# POWER.net
KiCad netlist of a schematic drawn in Altium Designer
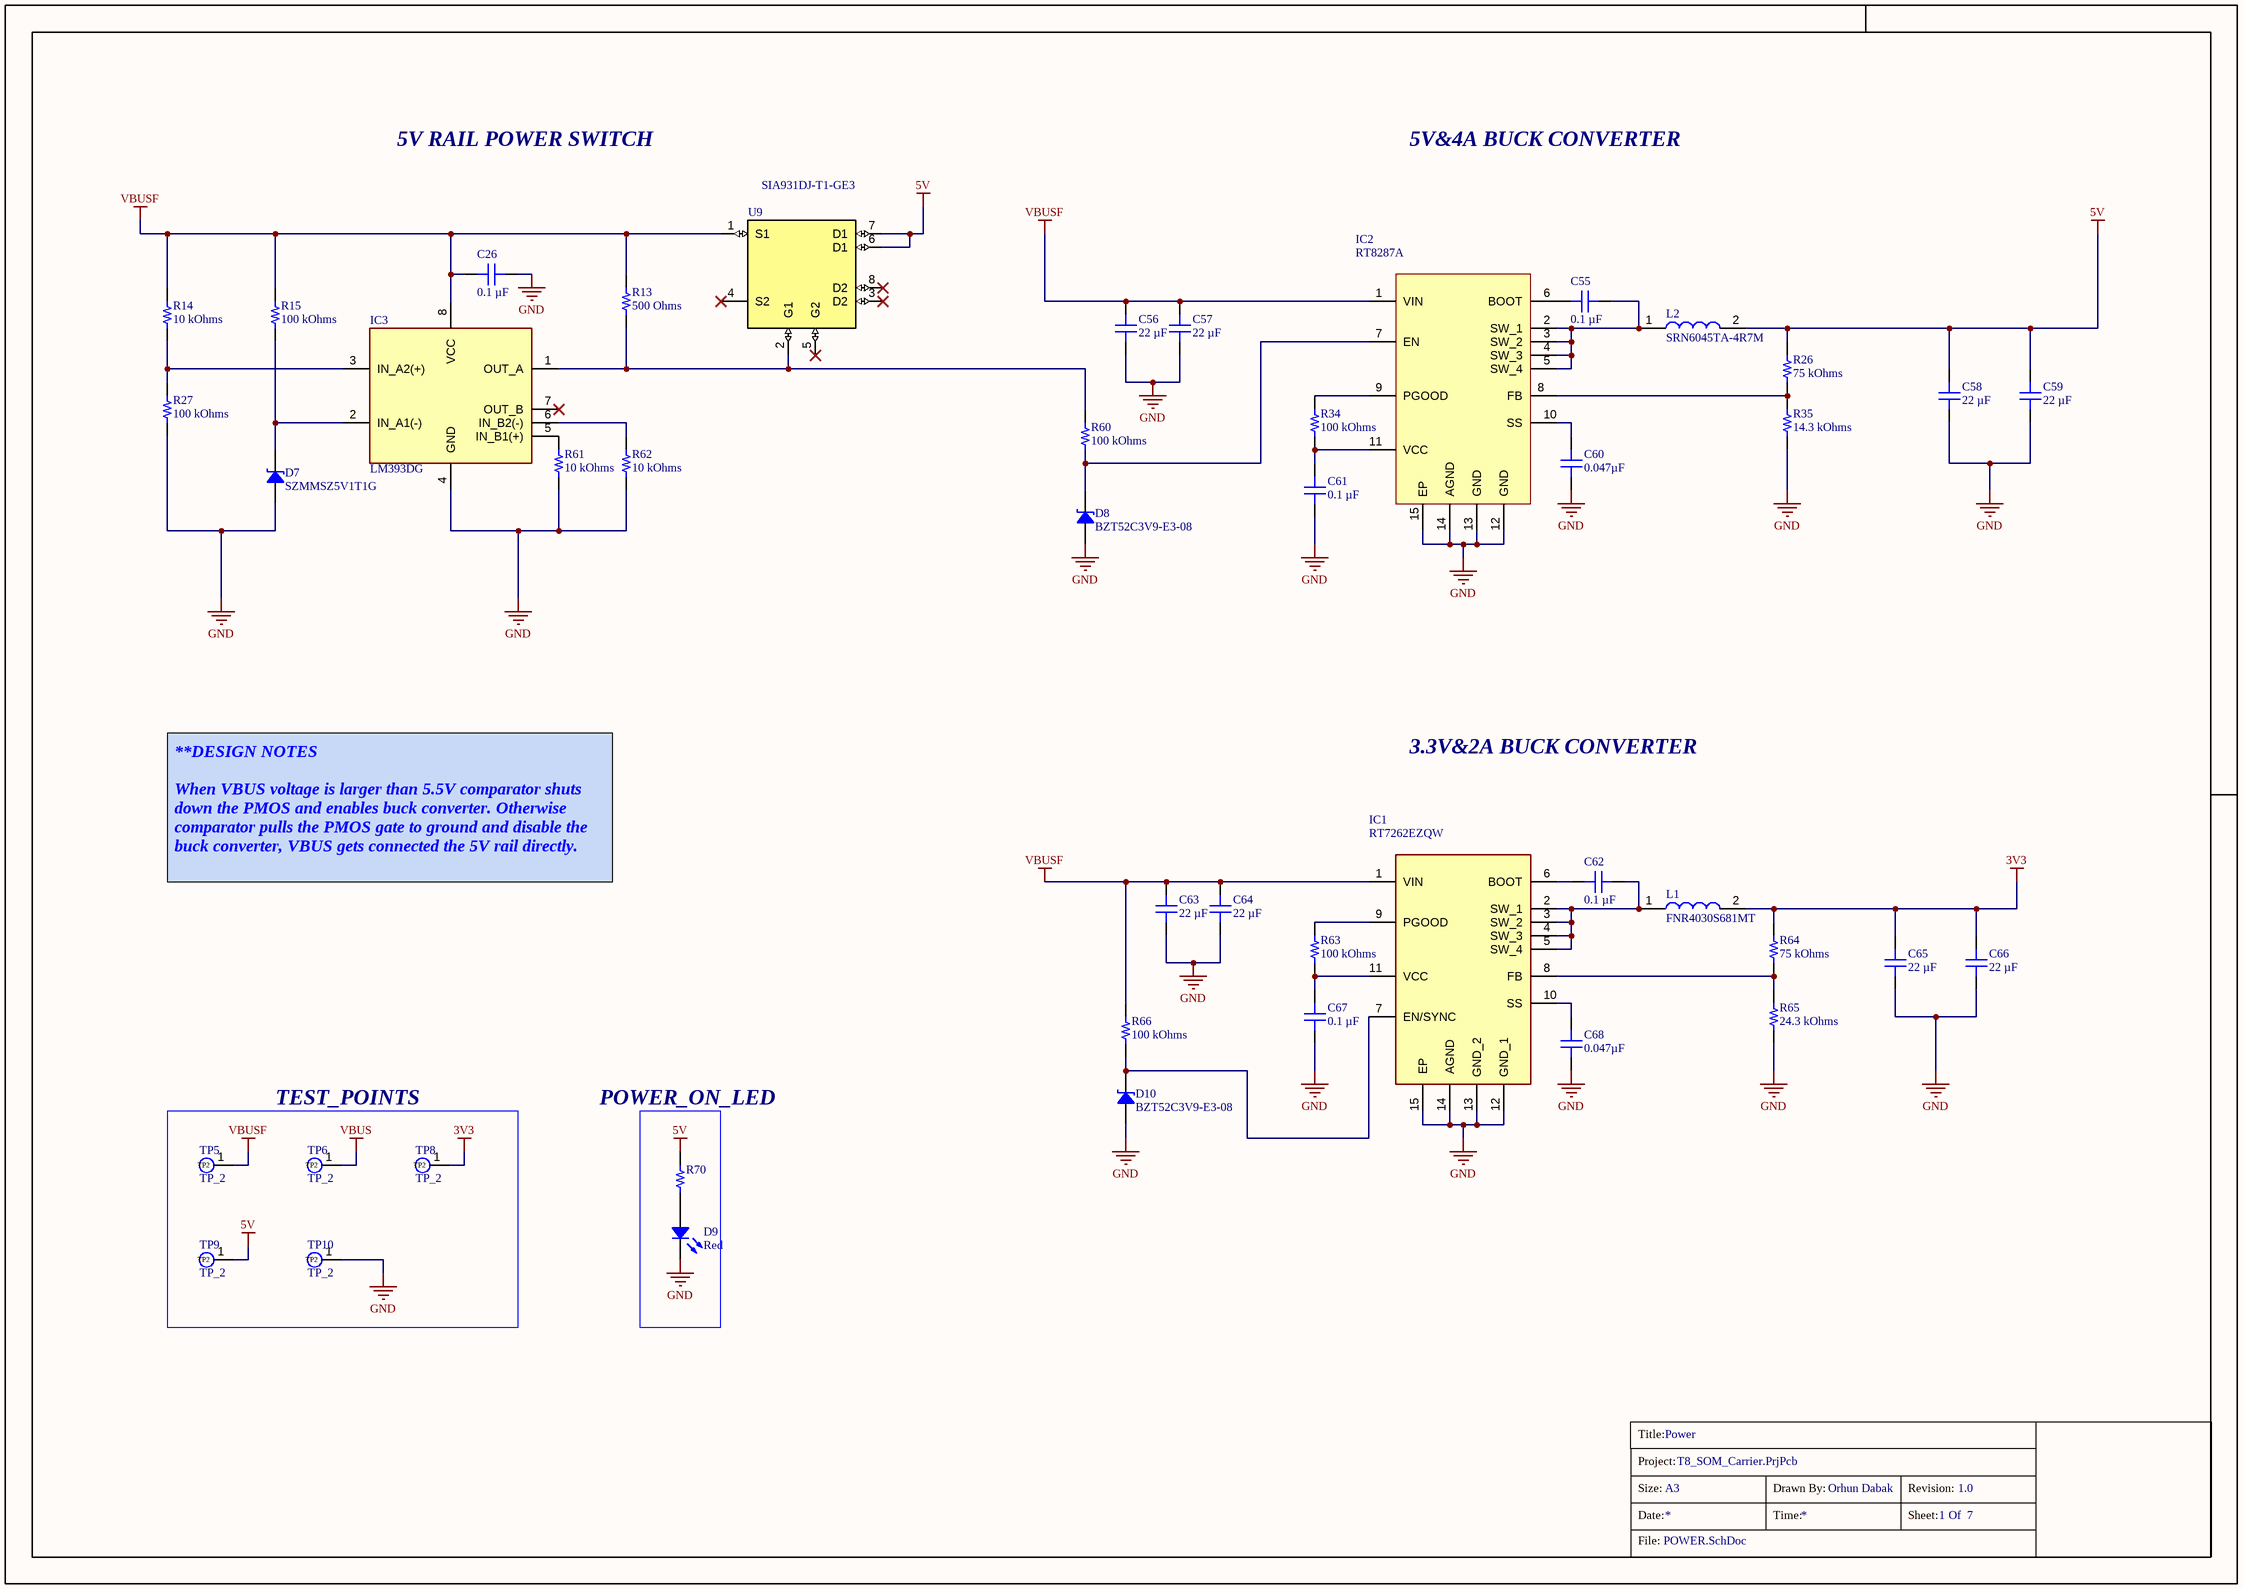
[diagram p0: POWER.SchDoc]

(export (version "E")
  (design (tool "Eeschema 10.0.6"))
  (components
    (comp (ref "C26")
      (value "0.1 µF")
      (footprint "CAP 0402_1005")
      (description "CAP CER 0.1UF 25V X7R 0402")
      (fields
        (field (name "PART NUMBER") "GCM155R71E104KE02D")
        (field (name "MANUFACTURER") "Murata Electronics")
      )
      (libsource (lib "Celestial Altium Library - altium_library") (part "Capacitor"))
    )
    (comp (ref "C55")
      (value "0.1 µF")
      (footprint "CAP 0402_1005")
      (description "CAP CER 0402 0.1UF 16V X7R 10%")
      (fields (field (name "PART NUMBER") "C0402C104K4RECAUTO") (field (name "MANUFACTURER") "KEMET"))
      (libsource (lib "Celestial Altium Library - altium_library") (part "Capacitor"))
    )
    (comp (ref "C56")
      (value "22 µF")
      (footprint "CAP 1812_4532 1.1MM")
      (description "CAP CER 22UF 25V X7R 1812")
      (fields
        (field (name "PART NUMBER") "CGA8P1X7R1E226M250KC")
        (field (name "MANUFACTURER") "TDK Corporation")
      )
      (libsource (lib "Celestial Altium Library - altium_library") (part "Capacitor"))
    )
    (comp (ref "C57")
      (value "22 µF")
      (footprint "CAP 1812_4532 1.1MM")
      (description "CAP CER 22UF 25V X7R 1812")
      (fields
        (field (name "PART NUMBER") "CGA8P1X7R1E226M250KC")
        (field (name "MANUFACTURER") "TDK Corporation")
      )
      (libsource (lib "Celestial Altium Library - altium_library") (part "Capacitor"))
    )
    (comp (ref "C58")
      (value "22 µF")
      (footprint "CAP 1210_3225 - 1MM")
      (description "CAP CER 22UF 16V X5R 1210")
      (fields
        (field (name "PART NUMBER") "C3225X5R1C226M250AA")
        (field (name "MANUFACTURER") "TDK Corporation")
      )
      (libsource (lib "Celestial Altium Library - altium_library") (part "Capacitor"))
    )
    (comp (ref "C59")
      (value "22 µF")
      (footprint "CAP 1210_3225 - 1MM")
      (description "CAP CER 22UF 16V X5R 1210")
      (fields
        (field (name "PART NUMBER") "C3225X5R1C226M250AA")
        (field (name "MANUFACTURER") "TDK Corporation")
      )
      (libsource (lib "Celestial Altium Library - altium_library") (part "Capacitor"))
    )
    (comp (ref "C60")
      (value "0.047µF")
      (footprint "CAP 0402_1005")
      (description "CAP CER 0.047UF 16V X5R 0402")
      (fields (field (name "PART NUMBER") "0402YD473KAT2A") (field (name "MANUFACTURER") "AVX Corporation"))
      (libsource (lib "Celestial Altium Library - altium_library") (part "Capacitor"))
    )
    (comp (ref "C61")
      (value "0.1 µF")
      (footprint "CAP 0402_1005")
      (description "CAP CER 0402 0.1UF 16V X7R 10%")
      (fields (field (name "PART NUMBER") "C0402C104K4RECAUTO") (field (name "MANUFACTURER") "KEMET"))
      (libsource (lib "Celestial Altium Library - altium_library") (part "Capacitor"))
    )
    (comp (ref "C62")
      (value "0.1 µF")
      (footprint "CAP 0402_1005")
      (description "CAP CER 0402 0.1UF 16V X7R 10%")
      (fields (field (name "PART NUMBER") "C0402C104K4RECAUTO") (field (name "MANUFACTURER") "KEMET"))
      (libsource (lib "Celestial Altium Library - altium_library") (part "Capacitor"))
    )
    (comp (ref "C63")
      (value "22 µF")
      (footprint "CAP 1812_4532 1.1MM")
      (description "CAP CER 22UF 25V X7R 1812")
      (fields
        (field (name "PART NUMBER") "CGA8P1X7R1E226M250KC")
        (field (name "MANUFACTURER") "TDK Corporation")
      )
      (libsource (lib "Celestial Altium Library - altium_library") (part "Capacitor"))
    )
    (comp (ref "C64")
      (value "22 µF")
      (footprint "CAP 1812_4532 1.1MM")
      (description "CAP CER 22UF 25V X7R 1812")
      (fields
        (field (name "PART NUMBER") "CGA8P1X7R1E226M250KC")
        (field (name "MANUFACTURER") "TDK Corporation")
      )
      (libsource (lib "Celestial Altium Library - altium_library") (part "Capacitor"))
    )
    (comp (ref "C65")
      (value "22 µF")
      (footprint "CAP 1210_3225 - 1MM")
      (description "CAP CER 22UF 16V X5R 1210")
      (fields
        (field (name "PART NUMBER") "C3225X5R1C226M250AA")
        (field (name "MANUFACTURER") "TDK Corporation")
      )
      (libsource (lib "Celestial Altium Library - altium_library") (part "Capacitor"))
    )
    (comp (ref "C66")
      (value "22 µF")
      (footprint "CAP 1210_3225 - 1MM")
      (description "CAP CER 22UF 16V X5R 1210")
      (fields
        (field (name "PART NUMBER") "C3225X5R1C226M250AA")
        (field (name "MANUFACTURER") "TDK Corporation")
      )
      (libsource (lib "Celestial Altium Library - altium_library") (part "Capacitor"))
    )
    (comp (ref "C67")
      (value "0.1 µF")
      (footprint "CAP 0402_1005")
      (description "CAP CER 0402 0.1UF 16V X7R 10%")
      (fields (field (name "PART NUMBER") "C0402C104K4RECAUTO") (field (name "MANUFACTURER") "KEMET"))
      (libsource (lib "Celestial Altium Library - altium_library") (part "Capacitor"))
    )
    (comp (ref "C68")
      (value "0.047µF")
      (footprint "CAP 0402_1005")
      (description "CAP CER 0.047UF 16V X5R 0402")
      (fields (field (name "PART NUMBER") "0402YD473KAT2A") (field (name "MANUFACTURER") "AVX Corporation"))
      (libsource (lib "Celestial Altium Library - altium_library") (part "Capacitor"))
    )
    (comp (ref "D7")
      (value "SZMMSZ5V1T1G")
      (footprint "SOD-123")
      (description "DIODE ZENER 5.1V 500MW SOD123")
      (fields (field (name "MANUFACTURER") "ON Semiconductor") (field (name "TOLERANCE") "±5%"))
      (libsource (lib "Celestial Altium Library - altium_library") (part "Diode Zener"))
    )
    (comp (ref "D8")
      (value "BZT52C3V9-E3-08")
      (footprint "SOD-123")
      (description "DIODE ZENER 3.9V 410MW SOD123")
      (fields
        (field (name "MANUFACTURER") "Vishay Semiconductor Diodes Division")
        (field (name "TOLERANCE") "±5%")
      )
      (libsource (lib "Celestial Altium Library - altium_library") (part "Diode Zener"))
    )
    (comp (ref "D9")
      (value "Red")
      (footprint "LED 0603_1608 RED")
      (description "LED RED CLEAR CHIP SMD")
      (fields (field (name "PART NUMBER") "LTST-C193KRKT-2A") (field (name "MANUFACTURER") "Lite-On Inc."))
      (libsource (lib "Celestial Altium Library - altium_library") (part "LED"))
    )
    (comp (ref "D10")
      (value "BZT52C3V9-E3-08")
      (footprint "SOD-123")
      (description "DIODE ZENER 3.9V 410MW SOD123")
      (fields
        (field (name "MANUFACTURER") "Vishay Semiconductor Diodes Division")
        (field (name "TOLERANCE") "±5%")
      )
      (libsource (lib "Celestial Altium Library - altium_library") (part "Diode Zener"))
    )
    (comp (ref "IC1")
      (value "RT7262EZQW")
      (footprint "SamacSys:SON50P300X400X80-15N")
      (description "Integrated Circuit")
      (libsource (lib "SamacSys") (part "RT7262EZQW"))
    )
    (comp (ref "IC2")
      (value "RT8287A")
      (footprint "SamacSys:SON50P300X400X80-15N")
      (description "Integrated Circuit")
      (libsource (lib "SamacSys") (part "RT8287A"))
    )
    (comp (ref "IC3")
      (value "LM393DG")
      (footprint "SamacSys:SOIC127P600X175-8N")
      (description "Integrated Circuit")
      (fields (field (name "MOUSER PART NUMBER") "863-LM393DG"))
      (libsource (lib "SamacSys") (part "LM393DG"))
    )
    (comp (ref "L1")
      (value "FNR4030S681MT")
      (footprint "SamacSys:INDPM4040X300N")
      (description "Inductor")
      (libsource (lib "SamacSys") (part "FNR4030S681MT"))
    )
    (comp (ref "L2")
      (value "SRN6045TA-4R7M")
      (footprint "SamacSys:SRN6045TA4R7M")
      (description "Inductor")
      (fields (field (name "MOUSER PART NUMBER") "652-SRN6045TA-4R7M"))
      (libsource (lib "SamacSys") (part "SRN6045TA-4R7M"))
    )
    (comp (ref "R13")
      (value "500 Ohms")
      (footprint "RES 0603_1608")
      (description "RES SMD 500 OHM 0.05% 1/10W 0603")
      (fields (field (name "PART NUMBER") "TNPU0603500RAZEN00") (field (name "MANUFACTURER") "Vishay Dale"))
      (libsource (lib "Celestial Altium Library - altium_library") (part "Resistor"))
    )
    (comp (ref "R14")
      (value "10 kOhms")
      (footprint "RES 0402_1005")
      (description "RES 10K OHM 0.1% 1/10W 0402")
      (fields
        (field (name "PART NUMBER") "RP73PF1E10KBTD")
        (field (name "MANUFACTURER") "TE Connectivity Passive Product")
      )
      (libsource (lib "Celestial Altium Library - altium_library") (part "Resistor"))
    )
    (comp (ref "R15")
      (value "100 kOhms")
      (footprint "RES 0402_1005")
      (description "RES 100K OHM 0.1% 1/10W 0402")
      (fields
        (field (name "PART NUMBER") "RP73PF1E100KBTD")
        (field (name "MANUFACTURER") "TE Connectivity Passive Product")
      )
      (libsource (lib "Celestial Altium Library - altium_library") (part "Resistor"))
    )
    (comp (ref "R26")
      (value "75 kOhms")
      (footprint "RES 0402_1005")
      (description "RES 75K OHM 1% 1/16W 0402")
      (fields (field (name "PART NUMBER") "RC0402FR-0775KL") (field (name "MANUFACTURER") "Yageo"))
      (libsource (lib "Celestial Altium Library - altium_library") (part "Resistor"))
    )
    (comp (ref "R27")
      (value "100 kOhms")
      (footprint "RES 0402_1005")
      (description "RES 100K OHM 0.1% 1/10W 0402")
      (fields
        (field (name "PART NUMBER") "RP73PF1E100KBTD")
        (field (name "MANUFACTURER") "TE Connectivity Passive Product")
      )
      (libsource (lib "Celestial Altium Library - altium_library") (part "Resistor"))
    )
    (comp (ref "R34")
      (value "100 kOhms")
      (footprint "RES 0402_1005")
      (description "RES 100K OHM 0.1% 1/10W 0402")
      (fields
        (field (name "PART NUMBER") "RP73PF1E100KBTD")
        (field (name "MANUFACTURER") "TE Connectivity Passive Product")
      )
      (libsource (lib "Celestial Altium Library - altium_library") (part "Resistor"))
    )
    (comp (ref "R35")
      (value "14.3 kOhms")
      (footprint "RES 0402_1005")
      (description "RES 14.3 KOHMS 0.1% 1/16W 0402")
      (fields
        (field (name "PART NUMBER") "RQ73C1E14K3BTD")
        (field (name "MANUFACTURER") "TE Connectivity Passive Product")
      )
      (libsource (lib "Celestial Altium Library - altium_library") (part "Resistor"))
    )
    (comp (ref "R60")
      (value "100 kOhms")
      (footprint "RES 0402_1005")
      (description "RES 100K OHM 0.1% 1/10W 0402")
      (fields
        (field (name "PART NUMBER") "RP73PF1E100KBTD")
        (field (name "MANUFACTURER") "TE Connectivity Passive Product")
      )
      (libsource (lib "Celestial Altium Library - altium_library") (part "Resistor"))
    )
    (comp (ref "R61")
      (value "10 kOhms")
      (footprint "RES 0402_1005")
      (description "RES 10K OHM 0.1% 1/10W 0402")
      (fields
        (field (name "PART NUMBER") "RP73PF1E10KBTD")
        (field (name "MANUFACTURER") "TE Connectivity Passive Product")
      )
      (libsource (lib "Celestial Altium Library - altium_library") (part "Resistor"))
    )
    (comp (ref "R62")
      (value "10 kOhms")
      (footprint "RES 0402_1005")
      (description "RES 10K OHM 0.1% 1/10W 0402")
      (fields
        (field (name "PART NUMBER") "RP73PF1E10KBTD")
        (field (name "MANUFACTURER") "TE Connectivity Passive Product")
      )
      (libsource (lib "Celestial Altium Library - altium_library") (part "Resistor"))
    )
    (comp (ref "R63")
      (value "100 kOhms")
      (footprint "RES 0402_1005")
      (description "RES 100K OHM 0.1% 1/10W 0402")
      (fields
        (field (name "PART NUMBER") "RP73PF1E100KBTD")
        (field (name "MANUFACTURER") "TE Connectivity Passive Product")
      )
      (libsource (lib "Celestial Altium Library - altium_library") (part "Resistor"))
    )
    (comp (ref "R64")
      (value "75 kOhms")
      (footprint "RES 0402_1005")
      (description "RES 75K OHM 1% 1/16W 0402")
      (fields (field (name "PART NUMBER") "RC0402FR-0775KL") (field (name "MANUFACTURER") "Yageo"))
      (libsource (lib "Celestial Altium Library - altium_library") (part "Resistor"))
    )
    (comp (ref "R65")
      (value "24.3 kOhms")
      (footprint "RES 0402_1005")
      (description "RES 24.3K OHM 1% 1/16W 0402")
      (fields (field (name "PART NUMBER") "RC0402FR-0724K3L") (field (name "MANUFACTURER") "Yageo"))
      (libsource (lib "Celestial Altium Library - altium_library") (part "Resistor"))
    )
    (comp (ref "R66")
      (value "100 kOhms")
      (footprint "RES 0402_1005")
      (description "RES 100K OHM 0.1% 1/10W 0402")
      (fields
        (field (name "PART NUMBER") "RP73PF1E100KBTD")
        (field (name "MANUFACTURER") "TE Connectivity Passive Product")
      )
      (libsource (lib "Celestial Altium Library - altium_library") (part "Resistor"))
    )
    (comp (ref "R70")
      (value "1 kOhms")
      (footprint "RES 0402_1005")
      (description "RES SMD 1K OHM 1% 1/16W 0402")
      (fields (field (name "PART NUMBER") "AC0402FR-071KL") (field (name "MANUFACTURER") "Yageo"))
      (libsource (lib "Celestial Altium Library - altium_library") (part "Resistor"))
    )
    (comp (ref "TP5")
      (value "TP_2")
      (footprint "TEST POINT")
      (description "1.5x1.5mm Test Point")
      (libsource (lib "FPGA_Based_SOM") (part "TEST POINT_2"))
    )
    (comp (ref "TP6")
      (value "TP_2")
      (footprint "TEST POINT")
      (description "1.5x1.5mm Test Point")
      (libsource (lib "FPGA_Based_SOM") (part "TEST POINT_2"))
    )
    (comp (ref "TP8")
      (value "TP_2")
      (footprint "TEST POINT")
      (description "1.5x1.5mm Test Point")
      (libsource (lib "FPGA_Based_SOM") (part "TEST POINT_2"))
    )
    (comp (ref "TP9")
      (value "TP_2")
      (footprint "TEST POINT")
      (description "1.5x1.5mm Test Point")
      (libsource (lib "FPGA_Based_SOM") (part "TEST POINT_2"))
    )
    (comp (ref "TP10")
      (value "TP_2")
      (footprint "TEST POINT")
      (description "1.5x1.5mm Test Point")
      (libsource (lib "FPGA_Based_SOM") (part "TEST POINT_2"))
    )
    (comp (ref "U9")
      (value "SIA931DJ-T1-GE3")
      (footprint "SIA931DJ-T1-GE3:MOSFET_T1-GE3_VIS")
      (description "No Description Available")
      (fields (field (name "COPYRIGHT") "Copyright (C) 2022 Ultra Librarian. All rights reserved."))
      (libsource (lib "SIA931DJ-T1-GE3") (part "SIA931DJ-T1-GE3"))
    )
  )
  (nets
    (net (code "1") (name "3V3") (class "Default")
      (node (ref "C65") (pin "2") (pinfunction "2_2") (pintype "passive"))
      (node (ref "C66") (pin "2") (pinfunction "2_2") (pintype "passive"))
      (node (ref "L1") (pin "2") (pinfunction "2_2") (pintype "passive"))
      (node (ref "R64") (pin "1") (pinfunction "1_1") (pintype "passive"))
      (node (ref "TP8") (pin "1") (pinfunction "TP2_1") (pintype "passive"))
    )
    (net (code "2") (name "5V") (class "Default")
      (node (ref "C58") (pin "2") (pinfunction "2_2") (pintype "passive"))
      (node (ref "C59") (pin "2") (pinfunction "2_2") (pintype "passive"))
      (node (ref "L2") (pin "2") (pinfunction "2_2") (pintype "passive"))
      (node (ref "R26") (pin "1") (pinfunction "1_1") (pintype "passive"))
      (node (ref "R70") (pin "2") (pinfunction "2_2") (pintype "passive"))
      (node (ref "TP9") (pin "1") (pinfunction "TP2_1") (pintype "passive"))
      (node (ref "U9") (pin "6") (pinfunction "D1_6") (pintype "bidirectional"))
      (node (ref "U9") (pin "7") (pinfunction "D1_7") (pintype "bidirectional"))
    )
    (net (code "3") (name "GND") (class "Default")
      (node (ref "C26") (pin "1") (pinfunction "1_1") (pintype "passive"))
      (node (ref "C56") (pin "1") (pinfunction "1_1") (pintype "passive"))
      (node (ref "C57") (pin "1") (pinfunction "1_1") (pintype "passive"))
      (node (ref "C58") (pin "1") (pinfunction "1_1") (pintype "passive"))
      (node (ref "C59") (pin "1") (pinfunction "1_1") (pintype "passive"))
      (node (ref "C60") (pin "1") (pinfunction "1_1") (pintype "passive"))
      (node (ref "C61") (pin "1") (pinfunction "1_1") (pintype "passive"))
      (node (ref "C63") (pin "1") (pinfunction "1_1") (pintype "passive"))
      (node (ref "C64") (pin "1") (pinfunction "1_1") (pintype "passive"))
      (node (ref "C65") (pin "1") (pinfunction "1_1") (pintype "passive"))
      (node (ref "C66") (pin "1") (pinfunction "1_1") (pintype "passive"))
      (node (ref "C67") (pin "1") (pinfunction "1_1") (pintype "passive"))
      (node (ref "C68") (pin "1") (pinfunction "1_1") (pintype "passive"))
      (node (ref "D10") (pin "1") (pinfunction "1_1") (pintype "passive"))
      (node (ref "D7") (pin "1") (pinfunction "1_1") (pintype "passive"))
      (node (ref "D8") (pin "1") (pinfunction "1_1") (pintype "passive"))
      (node (ref "D9") (pin "2") (pinfunction "2_2") (pintype "passive"))
      (node (ref "IC1") (pin "12") (pinfunction "GND_1_12") (pintype "passive"))
      (node (ref "IC1") (pin "13") (pinfunction "GND_2_13") (pintype "passive"))
      (node (ref "IC1") (pin "14") (pinfunction "AGND_14") (pintype "passive"))
      (node (ref "IC1") (pin "15") (pinfunction "EP_15") (pintype "passive"))
      (node (ref "IC2") (pin "12") (pinfunction "GND_12") (pintype "passive"))
      (node (ref "IC2") (pin "13") (pinfunction "GND_13") (pintype "passive"))
      (node (ref "IC2") (pin "14") (pinfunction "AGND_14") (pintype "passive"))
      (node (ref "IC3") (pin "4") (pinfunction "GND_4") (pintype "passive"))
      (node (ref "R27") (pin "1") (pinfunction "1_1") (pintype "passive"))
      (node (ref "R35") (pin "1") (pinfunction "1_1") (pintype "passive"))
      (node (ref "R61") (pin "1") (pinfunction "1_1") (pintype "passive"))
      (node (ref "R62") (pin "1") (pinfunction "1_1") (pintype "passive"))
      (node (ref "R65") (pin "1") (pinfunction "1_1") (pintype "passive"))
      (node (ref "TP10") (pin "1") (pinfunction "TP2_1") (pintype "passive"))
    )
    (net (code "4") (name "Net-(D9-Pad1)") (class "Default")
      (node (ref "D9") (pin "1") (pinfunction "1_1") (pintype "passive"))
      (node (ref "R70") (pin "1") (pinfunction "1_1") (pintype "passive"))
    )
    (net (code "5") (name "Net-(IC1-BOOT)") (class "Default")
      (node (ref "C62") (pin "1") (pinfunction "1_1") (pintype "passive"))
      (node (ref "IC1") (pin "6") (pinfunction "BOOT_6") (pintype "passive"))
    )
    (net (code "6") (name "Net-(IC1-EN{slash}SYNC)") (class "Default")
      (node (ref "D10") (pin "2") (pinfunction "2_2") (pintype "passive"))
      (node (ref "IC1") (pin "7") (pinfunction "EN/SYNC_7") (pintype "passive"))
      (node (ref "R66") (pin "1") (pinfunction "1_1") (pintype "passive"))
    )
    (net (code "7") (name "Net-(IC1-FB)") (class "Default")
      (node (ref "IC1") (pin "8") (pinfunction "FB_8") (pintype "passive"))
      (node (ref "R64") (pin "2") (pinfunction "2_2") (pintype "passive"))
      (node (ref "R65") (pin "2") (pinfunction "2_2") (pintype "passive"))
    )
    (net (code "8") (name "Net-(IC1-PGOOD)") (class "Default")
      (node (ref "IC1") (pin "9") (pinfunction "PGOOD_9") (pintype "passive"))
      (node (ref "R63") (pin "2") (pinfunction "2_2") (pintype "passive"))
    )
    (net (code "9") (name "Net-(IC1-SS)") (class "Default")
      (node (ref "C68") (pin "2") (pinfunction "2_2") (pintype "passive"))
      (node (ref "IC1") (pin "10") (pinfunction "SS_10") (pintype "passive"))
    )
    (net (code "10") (name "Net-(IC1-SW_1)") (class "Default")
      (node (ref "C62") (pin "2") (pinfunction "2_2") (pintype "passive"))
      (node (ref "IC1") (pin "2") (pinfunction "SW_1_2") (pintype "passive"))
      (node (ref "IC1") (pin "3") (pinfunction "SW_2_3") (pintype "passive"))
      (node (ref "IC1") (pin "4") (pinfunction "SW_3_4") (pintype "passive"))
      (node (ref "IC1") (pin "5") (pinfunction "SW_4_5") (pintype "passive"))
      (node (ref "L1") (pin "1") (pinfunction "1_1") (pintype "passive"))
    )
    (net (code "11") (name "Net-(IC1-VCC)") (class "Default")
      (node (ref "C67") (pin "2") (pinfunction "2_2") (pintype "passive"))
      (node (ref "IC1") (pin "11") (pinfunction "VCC_11") (pintype "passive"))
      (node (ref "R63") (pin "1") (pinfunction "1_1") (pintype "passive"))
    )
    (net (code "12") (name "Net-(IC2-BOOT)") (class "Default")
      (node (ref "C55") (pin "1") (pinfunction "1_1") (pintype "passive"))
      (node (ref "IC2") (pin "6") (pinfunction "BOOT_6") (pintype "passive"))
    )
    (net (code "13") (name "Net-(IC2-EN)") (class "Default")
      (node (ref "D8") (pin "2") (pinfunction "2_2") (pintype "passive"))
      (node (ref "IC2") (pin "7") (pinfunction "EN_7") (pintype "passive"))
      (node (ref "R60") (pin "1") (pinfunction "1_1") (pintype "passive"))
    )
    (net (code "14") (name "Net-(IC2-PGOOD)") (class "Default")
      (node (ref "IC2") (pin "9") (pinfunction "PGOOD_9") (pintype "passive"))
      (node (ref "R34") (pin "2") (pinfunction "2_2") (pintype "passive"))
    )
    (net (code "15") (name "Net-(IC2-SS)") (class "Default")
      (node (ref "C60") (pin "2") (pinfunction "2_2") (pintype "passive"))
      (node (ref "IC2") (pin "10") (pinfunction "SS_10") (pintype "passive"))
    )
    (net (code "16") (name "Net-(IC2-SW_1)") (class "Default")
      (node (ref "C55") (pin "2") (pinfunction "2_2") (pintype "passive"))
      (node (ref "IC2") (pin "2") (pinfunction "SW_1_2") (pintype "passive"))
      (node (ref "IC2") (pin "3") (pinfunction "SW_2_3") (pintype "passive"))
      (node (ref "IC2") (pin "4") (pinfunction "SW_3_4") (pintype "passive"))
      (node (ref "IC2") (pin "5") (pinfunction "SW_4_5") (pintype "passive"))
      (node (ref "L2") (pin "1") (pinfunction "1_1") (pintype "passive"))
    )
    (net (code "17") (name "Net-(IC2-VCC)") (class "Default")
      (node (ref "C61") (pin "2") (pinfunction "2_2") (pintype "passive"))
      (node (ref "IC2") (pin "11") (pinfunction "VCC_11") (pintype "passive"))
      (node (ref "R34") (pin "1") (pinfunction "1_1") (pintype "passive"))
    )
    (net (code "18") (name "Net-(IC3-IN_A1(-))") (class "Default")
      (node (ref "D7") (pin "2") (pinfunction "2_2") (pintype "passive"))
      (node (ref "IC3") (pin "2") (pinfunction "IN_A1(-)_2") (pintype "passive"))
      (node (ref "R15") (pin "1") (pinfunction "1_1") (pintype "passive"))
    )
    (net (code "19") (name "Net-(IC3-IN_A2(+))") (class "Default")
      (node (ref "IC3") (pin "3") (pinfunction "IN_A2(+)_3") (pintype "passive"))
      (node (ref "R14") (pin "1") (pinfunction "1_1") (pintype "passive"))
      (node (ref "R27") (pin "2") (pinfunction "2_2") (pintype "passive"))
    )
    (net (code "20") (name "Net-(IC3-IN_B1(+))") (class "Default")
      (node (ref "IC3") (pin "5") (pinfunction "IN_B1(+)_5") (pintype "passive"))
      (node (ref "R61") (pin "2") (pinfunction "2_2") (pintype "passive"))
    )
    (net (code "21") (name "Net-(IC3-IN_B2(-))") (class "Default")
      (node (ref "IC3") (pin "6") (pinfunction "IN_B2(-)_6") (pintype "passive"))
      (node (ref "R62") (pin "2") (pinfunction "2_2") (pintype "passive"))
    )
    (net (code "22") (name "Net-(IC3-OUT_A)") (class "Default")
      (node (ref "IC3") (pin "1") (pinfunction "OUT_A_1") (pintype "passive"))
      (node (ref "R13") (pin "1") (pinfunction "1_1") (pintype "passive"))
      (node (ref "R60") (pin "2") (pinfunction "2_2") (pintype "passive"))
      (node (ref "U9") (pin "2") (pinfunction "G1_2") (pintype "bidirectional"))
    )
    (net (code "23") (name "Net-(R26-Pad2)") (class "Default")
      (node (ref "R26") (pin "2") (pinfunction "2_2") (pintype "passive"))
      (node (ref "R35") (pin "2") (pinfunction "2_2") (pintype "passive"))
    )
    (net (code "24") (name "VBUS") (class "Default")
      (node (ref "TP6") (pin "1") (pinfunction "TP2_1") (pintype "passive"))
    )
    (net (code "25") (name "VBUSF") (class "Default")
      (node (ref "C26") (pin "2") (pinfunction "2_2") (pintype "passive"))
      (node (ref "C56") (pin "2") (pinfunction "2_2") (pintype "passive"))
      (node (ref "C57") (pin "2") (pinfunction "2_2") (pintype "passive"))
      (node (ref "C63") (pin "2") (pinfunction "2_2") (pintype "passive"))
      (node (ref "C64") (pin "2") (pinfunction "2_2") (pintype "passive"))
      (node (ref "IC1") (pin "1") (pinfunction "VIN_1") (pintype "passive"))
      (node (ref "IC2") (pin "1") (pinfunction "VIN_1") (pintype "passive"))
      (node (ref "IC3") (pin "8") (pinfunction "VCC_8") (pintype "passive"))
      (node (ref "R13") (pin "2") (pinfunction "2_2") (pintype "passive"))
      (node (ref "R14") (pin "2") (pinfunction "2_2") (pintype "passive"))
      (node (ref "R15") (pin "2") (pinfunction "2_2") (pintype "passive"))
      (node (ref "R66") (pin "2") (pinfunction "2_2") (pintype "passive"))
      (node (ref "TP5") (pin "1") (pinfunction "TP2_1") (pintype "passive"))
      (node (ref "U9") (pin "1") (pinfunction "S1_1") (pintype "bidirectional"))
    )
    (net (code "26") (name "unconnected-(IC2-EP-Pad15)") (class "Default")
      (node (ref "IC2") (pin "15") (pinfunction "EP_15") (pintype "passive"))
    )
    (net (code "27") (name "unconnected-(IC2-FB-Pad8)") (class "Default")
      (node (ref "IC2") (pin "8") (pinfunction "FB_8") (pintype "passive"))
    )
    (net (code "28") (name "unconnected-(IC3-OUT_B-Pad7)") (class "Default")
      (node (ref "IC3") (pin "7") (pinfunction "OUT_B_7") (pintype "passive+no_connect"))
    )
    (net (code "29") (name "unconnected-(U9-D2-Pad3)") (class "Default")
      (node (ref "U9") (pin "3") (pinfunction "D2_3") (pintype "bidirectional+no_connect"))
    )
    (net (code "30") (name "unconnected-(U9-D2-Pad8)") (class "Default")
      (node (ref "U9") (pin "8") (pinfunction "D2_8") (pintype "bidirectional+no_connect"))
    )
    (net (code "31") (name "unconnected-(U9-G2-Pad5)") (class "Default")
      (node (ref "U9") (pin "5") (pinfunction "G2_5") (pintype "bidirectional+no_connect"))
    )
    (net (code "32") (name "unconnected-(U9-S2-Pad4)") (class "Default")
      (node (ref "U9") (pin "4") (pinfunction "S2_4") (pintype "passive+no_connect"))
    )
  )
)
